# Metacarpal.net
KiCad netlist of a schematic drawn in Altium Designer
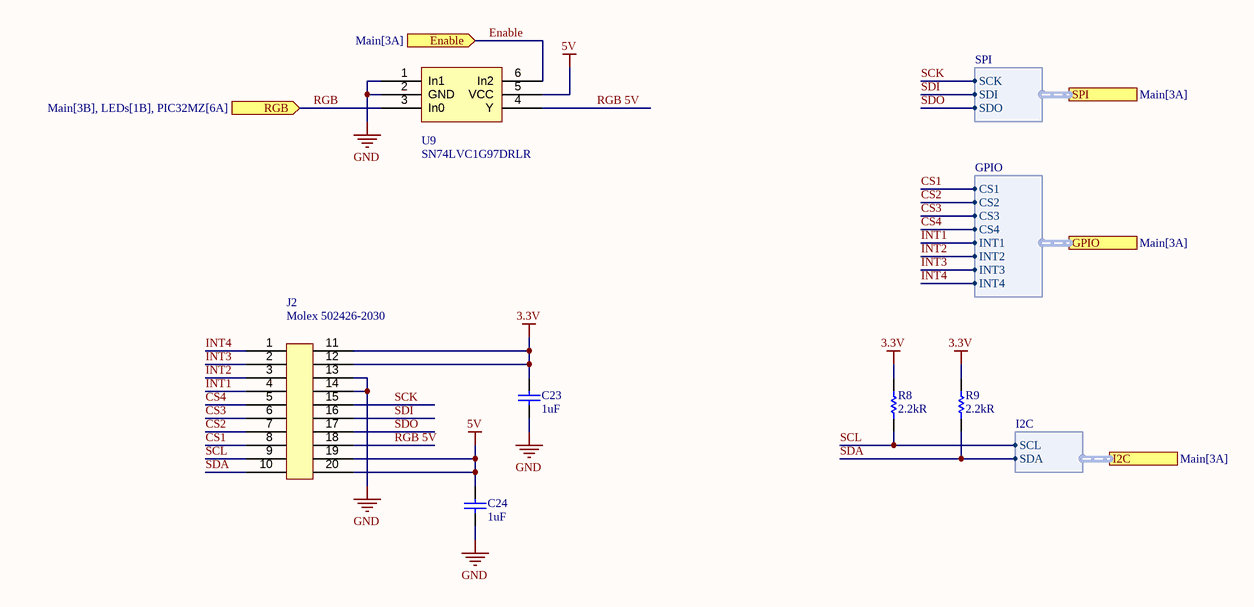
[diagram p0: Metacarpal.SchDoc]

(export (version "E")
  (design (tool "Eeschema 10.0.6"))
  (components
    (comp (ref "C23") (value "1uF") (footprint "Capacitor 0402") (libsource (lib "x-io") (part "Capacitor")))
    (comp (ref "C24") (value "1uF") (footprint "Capacitor 0402") (libsource (lib "x-io") (part "Capacitor")))
    (comp (ref "J2")
      (value "Molex 502426-2030")
      (footprint "Molex 502426-2030")
      (libsource (lib "x-io") (part "Molex 502426-2030"))
    )
    (comp (ref "R8") (value "2.2kR") (footprint "Resistor 0402") (libsource (lib "x-io") (part "Resistor")))
    (comp (ref "R9") (value "2.2kR") (footprint "Resistor 0402") (libsource (lib "x-io") (part "Resistor")))
    (comp (ref "U9")
      (value "SN74LVC1G97DRLR")
      (footprint "SOT-666")
      (libsource (lib "x-io") (part "SN74LVC1G97DRLR"))
    )
  )
  (nets
    (net (code "4") (name "/CS1") (class "Default")
      (node (ref "J2") (pin "8") (pinfunction "8_8") (pintype "passive"))
    )
    (net (code "5") (name "/CS2") (class "Default")
      (node (ref "J2") (pin "7") (pinfunction "7_7") (pintype "passive"))
    )
    (net (code "6") (name "/CS3") (class "Default")
      (node (ref "J2") (pin "6") (pinfunction "6_6") (pintype "passive"))
    )
    (net (code "7") (name "/CS4") (class "Default")
      (node (ref "J2") (pin "5") (pinfunction "5_5") (pintype "passive"))
    )
    (net (code "8") (name "/Enable") (class "Default")
      (node (ref "U9") (pin "6") (pinfunction "In2_6") (pintype "passive"))
    )
    (net (code "9") (name "/INT1") (class "Default")
      (node (ref "J2") (pin "4") (pinfunction "4_4") (pintype "passive"))
    )
    (net (code "10") (name "/INT2") (class "Default")
      (node (ref "J2") (pin "3") (pinfunction "3_3") (pintype "passive"))
    )
    (net (code "11") (name "/INT3") (class "Default")
      (node (ref "J2") (pin "2") (pinfunction "2_2") (pintype "passive"))
    )
    (net (code "12") (name "/INT4") (class "Default")
      (node (ref "J2") (pin "1") (pinfunction "1_1") (pintype "passive"))
    )
    (net (code "13") (name "/RGB") (class "Default")
      (node (ref "U9") (pin "3") (pinfunction "In0_3") (pintype "passive"))
    )
    (net (code "14") (name "/RGB 5V") (class "Default")
      (node (ref "J2") (pin "18") (pinfunction "18_18") (pintype "passive"))
      (node (ref "U9") (pin "4") (pinfunction "Y_4") (pintype "passive"))
    )
    (net (code "15") (name "/SCK") (class "Default")
      (node (ref "J2") (pin "15") (pinfunction "15_15") (pintype "passive"))
    )
    (net (code "16") (name "/SCL") (class "Default")
      (node (ref "J2") (pin "9") (pinfunction "9_9") (pintype "passive"))
      (node (ref "R8") (pin "1") (pinfunction "1_1") (pintype "passive"))
    )
    (net (code "17") (name "/SDA") (class "Default")
      (node (ref "J2") (pin "10") (pinfunction "10_10") (pintype "passive"))
      (node (ref "R9") (pin "1") (pinfunction "1_1") (pintype "passive"))
    )
    (net (code "18") (name "/SDI") (class "Default")
      (node (ref "J2") (pin "16") (pinfunction "16_16") (pintype "passive"))
    )
    (net (code "19") (name "/SDO") (class "Default")
      (node (ref "J2") (pin "17") (pinfunction "17_17") (pintype "passive"))
    )
    (net (code "23") (name "3.3V") (class "Default")
      (node (ref "C23") (pin "2") (pinfunction "2_2") (pintype "passive"))
      (node (ref "J2") (pin "11") (pinfunction "11_11") (pintype "passive"))
      (node (ref "J2") (pin "12") (pinfunction "12_12") (pintype "passive"))
      (node (ref "R8") (pin "2") (pinfunction "2_2") (pintype "passive"))
      (node (ref "R9") (pin "2") (pinfunction "2_2") (pintype "passive"))
    )
    (net (code "24") (name "5V") (class "Default")
      (node (ref "C24") (pin "2") (pinfunction "2_2") (pintype "passive"))
      (node (ref "J2") (pin "19") (pinfunction "19_19") (pintype "passive"))
      (node (ref "J2") (pin "20") (pinfunction "20_20") (pintype "passive"))
      (node (ref "U9") (pin "5") (pinfunction "VCC_5") (pintype "passive"))
    )
    (net (code "25") (name "GND") (class "Default")
      (node (ref "C23") (pin "1") (pinfunction "1_1") (pintype "passive"))
      (node (ref "C24") (pin "1") (pinfunction "1_1") (pintype "passive"))
      (node (ref "J2") (pin "13") (pinfunction "13_13") (pintype "passive"))
      (node (ref "J2") (pin "14") (pinfunction "14_14") (pintype "passive"))
      (node (ref "U9") (pin "1") (pinfunction "In1_1") (pintype "passive"))
      (node (ref "U9") (pin "2") (pinfunction "GND_2") (pintype "passive"))
    )
  )
)
